# power_supply.net
KiCad netlist of a schematic drawn in Altium Designer
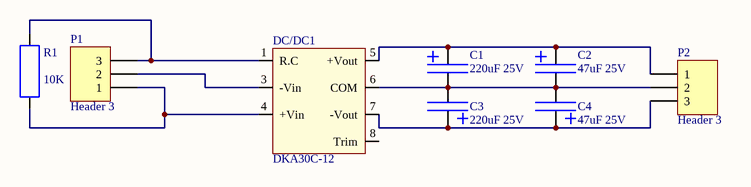
[diagram p0: power_supply.SchDoc]

(export (version "E")
  (design (tool "Eeschema 10.0.6"))
  (components
    (comp (ref "C1")
      (value "220uF 25V")
      (footprint "Cond 6mm 25V")
      (libsource (lib "A_H_sch_lib") (part "Cond_polar"))
    )
    (comp (ref "C2")
      (value "47uF 25V")
      (footprint "Cond 6mm 25V")
      (libsource (lib "A_H_sch_lib") (part "Cond_polar"))
    )
    (comp (ref "C3")
      (value "220uF 25V")
      (footprint "Cond 6mm 25V")
      (libsource (lib "A_H_sch_lib") (part "Cond_polar"))
    )
    (comp (ref "C4")
      (value "47uF 25V")
      (footprint "Cond 6mm 25V")
      (libsource (lib "A_H_sch_lib") (part "Cond_polar"))
    )
    (comp (ref "DC/DC1")
      (value "DKA30C-12")
      (footprint "A_H_pcb_lib:MW_DKA30C-12")
      (libsource (lib "A_H_sch_lib") (part "MW_DKA30C-12"))
    )
    (comp (ref "P1")
      (value "Header 3")
      (footprint "HDR1X3")
      (description "Header, 3-Pin")
      (fields (field (name "PUBLISHER") "Altium Limited"))
      (libsource (lib "") (part "Header 3_1"))
    )
    (comp (ref "P2")
      (value "Header 3")
      (footprint "HDR1X3")
      (description "Header, 3-Pin")
      (fields (field (name "PUBLISHER") "Altium Limited"))
      (libsource (lib "Miscellaneous Connectors") (part "Header 3"))
    )
    (comp (ref "R1") (value "10K") (footprint "R0805") (libsource (lib "A_H_sch_lib") (part "Resistor")))
  )
  (nets
    (net (code "1") (name "Net-(DC/DC1-+Vin)") (class "Default")
      (node (ref "DC/DC1") (pin "4") (pinfunction "+Vin_4") (pintype "passive"))
      (node (ref "P1") (pin "1") (pinfunction "1_1") (pintype "passive"))
      (node (ref "R1") (pin "1") (pinfunction "1_1") (pintype "passive"))
    )
    (net (code "2") (name "Net-(DC/DC1-+Vout)") (class "Default")
      (node (ref "C1") (pin "1") (pinfunction "1_1") (pintype "passive"))
      (node (ref "C2") (pin "1") (pinfunction "1_1") (pintype "passive"))
      (node (ref "DC/DC1") (pin "5") (pinfunction "+Vout_5") (pintype "passive"))
      (node (ref "P2") (pin "1") (pinfunction "1_1") (pintype "passive"))
    )
    (net (code "3") (name "Net-(DC/DC1--Vin)") (class "Default")
      (node (ref "DC/DC1") (pin "3") (pinfunction "-Vin_3") (pintype "passive"))
      (node (ref "P1") (pin "2") (pinfunction "2_2") (pintype "passive"))
    )
    (net (code "4") (name "Net-(DC/DC1--Vout)") (class "Default")
      (node (ref "C3") (pin "1") (pinfunction "1_1") (pintype "passive"))
      (node (ref "C4") (pin "1") (pinfunction "1_1") (pintype "passive"))
      (node (ref "DC/DC1") (pin "7") (pinfunction "-Vout_7") (pintype "passive"))
      (node (ref "P2") (pin "3") (pinfunction "3_3") (pintype "passive"))
    )
    (net (code "5") (name "Net-(DC/DC1-COM)") (class "Default")
      (node (ref "C1") (pin "2") (pinfunction "2_2") (pintype "passive"))
      (node (ref "C2") (pin "2") (pinfunction "2_2") (pintype "passive"))
      (node (ref "C3") (pin "2") (pinfunction "2_2") (pintype "passive"))
      (node (ref "C4") (pin "2") (pinfunction "2_2") (pintype "passive"))
      (node (ref "DC/DC1") (pin "6") (pinfunction "COM_6") (pintype "passive"))
      (node (ref "P2") (pin "2") (pinfunction "2_2") (pintype "passive"))
    )
    (net (code "6") (name "Net-(DC/DC1-R.C)") (class "Default")
      (node (ref "DC/DC1") (pin "1") (pinfunction "R.C_1") (pintype "passive"))
      (node (ref "P1") (pin "3") (pinfunction "3_3") (pintype "passive"))
      (node (ref "R1") (pin "2") (pinfunction "2_2") (pintype "passive"))
    )
    (net (code "7") (name "unconnected-(DC/DC1-Trim-Pad8)") (class "Default")
      (node (ref "DC/DC1") (pin "8") (pinfunction "Trim_8") (pintype "passive"))
    )
  )
)
